# S7CAS-PLEIADES-CARTE-MERE_P07_USB.net
KiCad netlist of a schematic drawn in Altium Designer
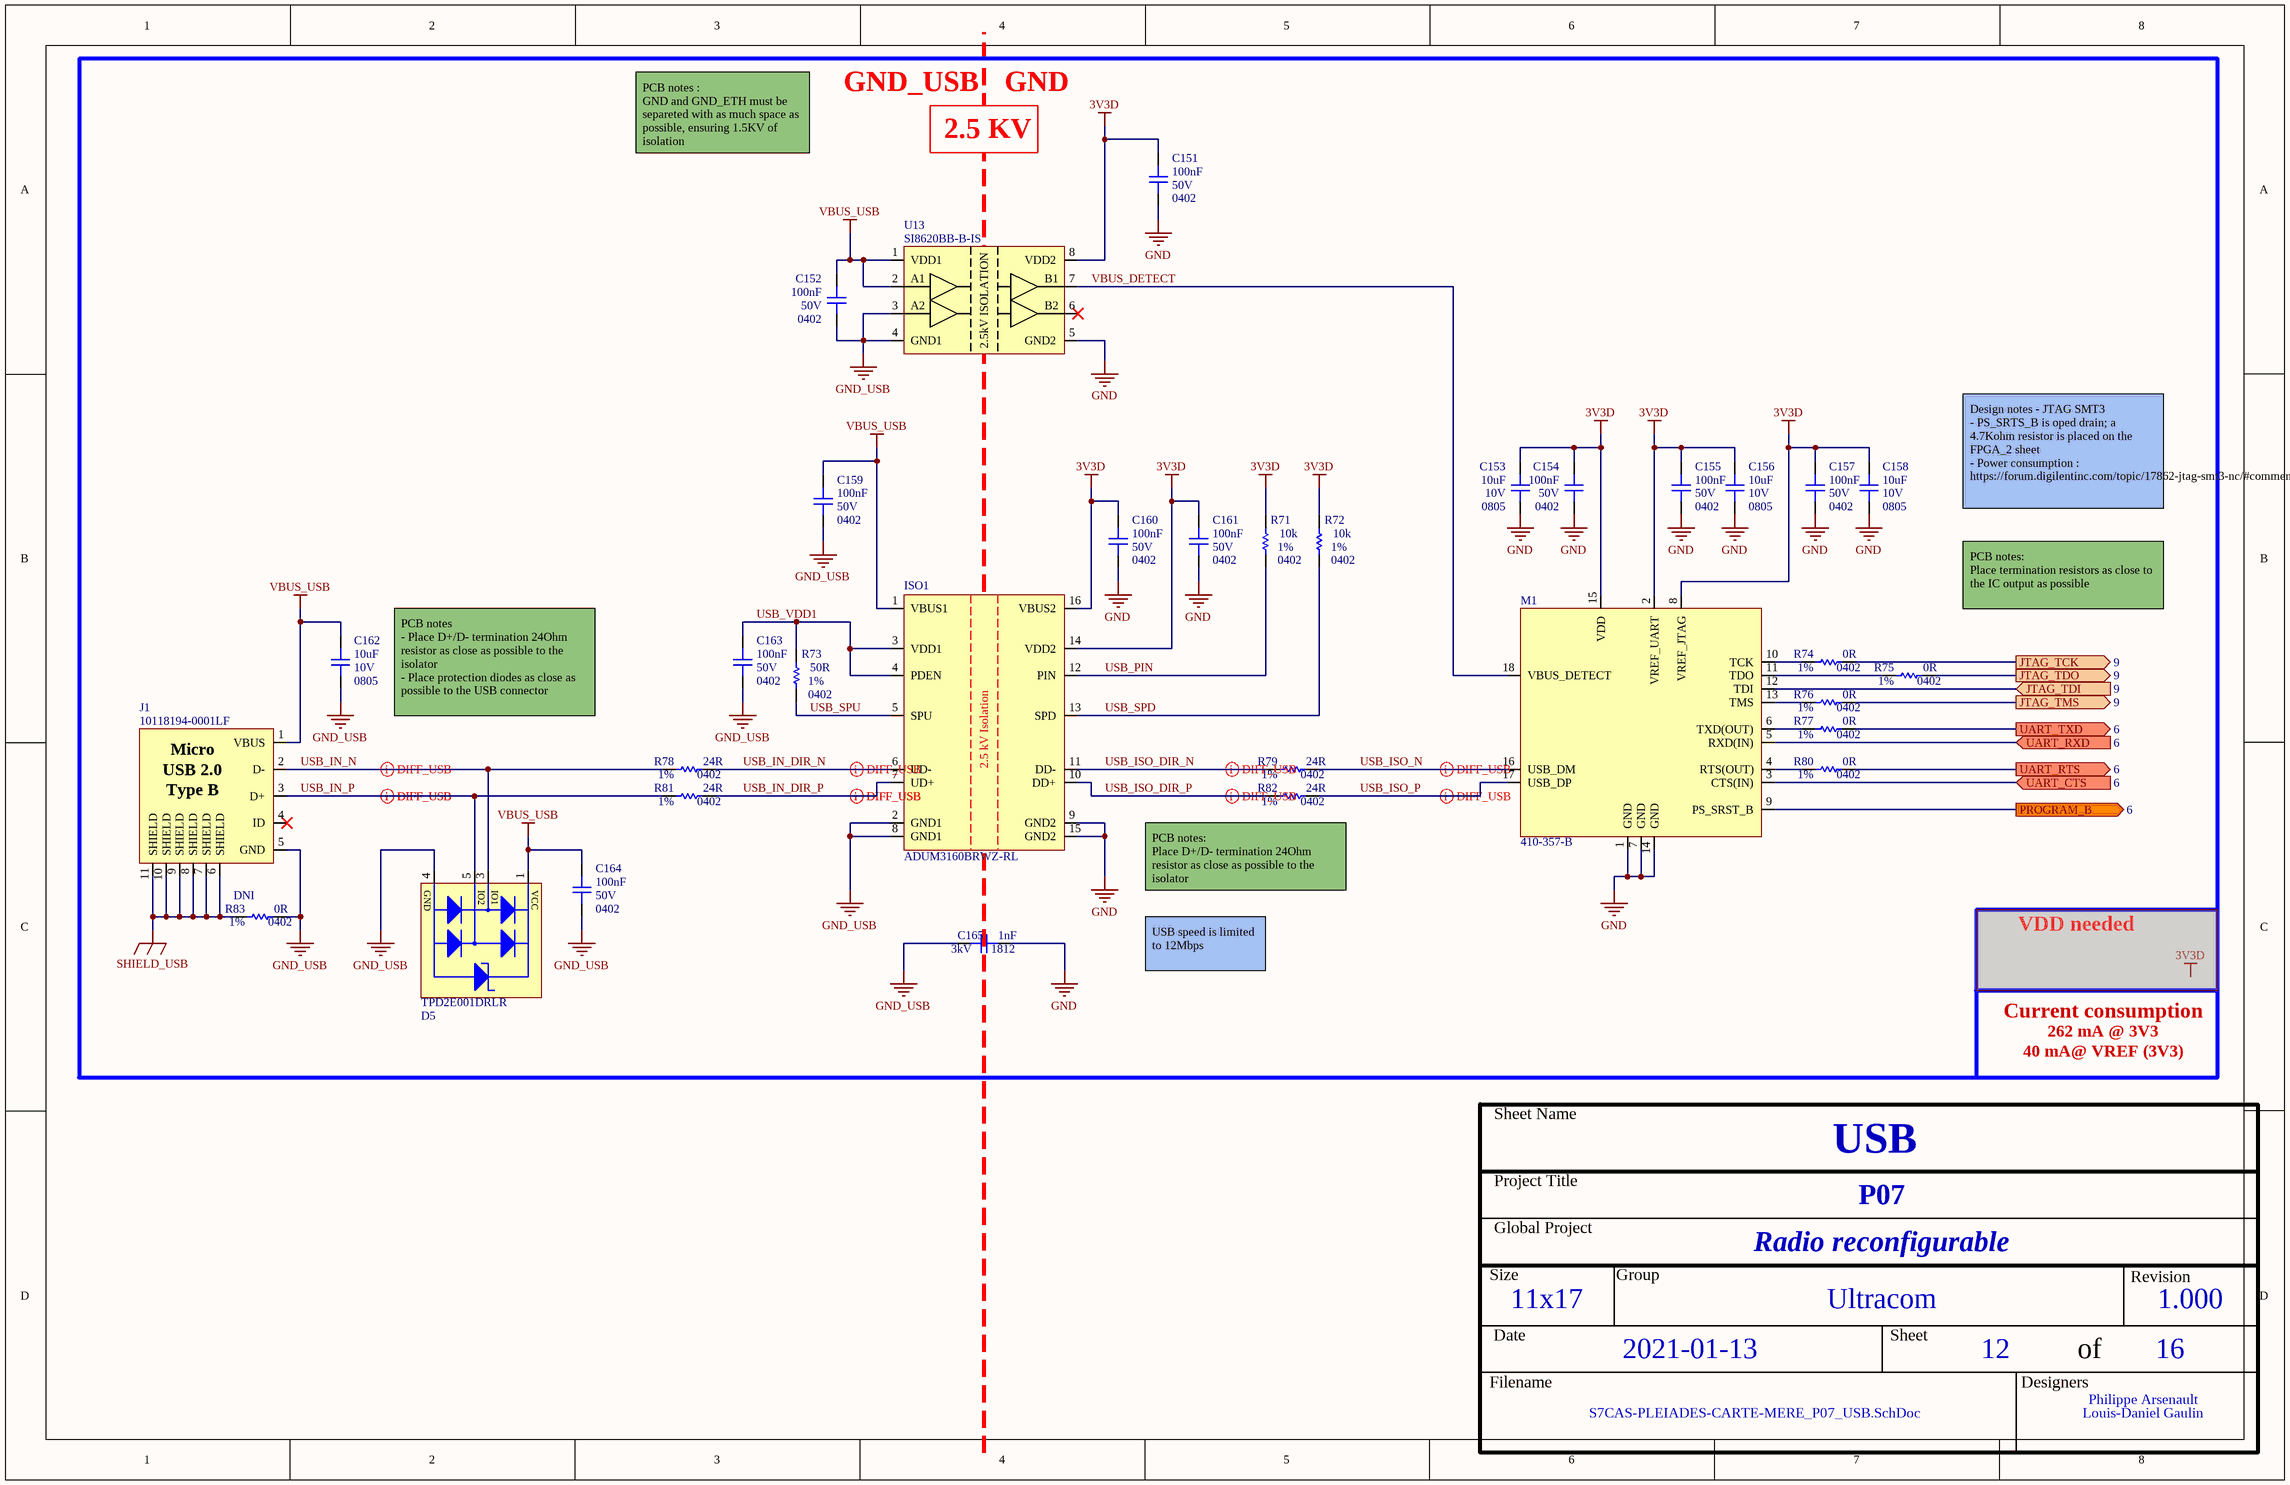
[diagram p0: S7CAS-PLEIADES-CARTE-MERE_P07_USB.SchDoc]

(export (version "E")
  (design (tool "Eeschema 10.0.6"))
  (components
    (comp (ref "C151")
      (value "100nF")
      (footprint "CAP_0402")
      (description "CAP - 0402")
      (fields
        (field (name "VOLTAGE") "50V")
        (field (name "PACKAGE") "0402")
        (field (name "CREATEDBY") "Jonathan Bouchard")
      )
      (libsource (lib "S7CAS_LIB2021") (part "CAP - 0402"))
    )
    (comp (ref "C152")
      (value "100nF")
      (footprint "CAP_0402")
      (description "CAP - 0402")
      (fields
        (field (name "VOLTAGE") "50V")
        (field (name "PACKAGE") "0402")
        (field (name "CREATEDBY") "Jonathan Bouchard")
      )
      (libsource (lib "S7CAS_LIB2021") (part "CAP - 0402"))
    )
    (comp (ref "C153")
      (value "10uF")
      (footprint "CAP_0805")
      (description "CAP - 0805")
      (fields
        (field (name "MFG") "CL21B106KPQNNNE")
        (field (name "VOLTAGE") "10V")
        (field (name "PACKAGE") "0805")
        (field (name "CREATEDBY") "Jonathan Bouchard")
      )
      (libsource (lib "S7CAS_LIB2021") (part "CAP - 0805"))
    )
    (comp (ref "C154")
      (value "100nF")
      (footprint "CAP_0402")
      (description "CAP - 0402")
      (fields
        (field (name "VOLTAGE") "50V")
        (field (name "PACKAGE") "0402")
        (field (name "CREATEDBY") "Jonathan Bouchard")
      )
      (libsource (lib "S7CAS_LIB2021") (part "CAP - 0402"))
    )
    (comp (ref "C155")
      (value "100nF")
      (footprint "CAP_0402")
      (description "CAP - 0402")
      (fields
        (field (name "VOLTAGE") "50V")
        (field (name "PACKAGE") "0402")
        (field (name "CREATEDBY") "Jonathan Bouchard")
      )
      (libsource (lib "S7CAS_LIB2021") (part "CAP - 0402"))
    )
    (comp (ref "C156")
      (value "10uF")
      (footprint "CAP_0805")
      (description "CAP - 0805")
      (fields
        (field (name "MFG") "CL21B106KPQNNNE")
        (field (name "VOLTAGE") "10V")
        (field (name "PACKAGE") "0805")
        (field (name "CREATEDBY") "Jonathan Bouchard")
      )
      (libsource (lib "S7CAS_LIB2021") (part "CAP - 0805"))
    )
    (comp (ref "C157")
      (value "100nF")
      (footprint "CAP_0402")
      (description "CAP - 0402")
      (fields
        (field (name "VOLTAGE") "50V")
        (field (name "PACKAGE") "0402")
        (field (name "CREATEDBY") "Jonathan Bouchard")
      )
      (libsource (lib "S7CAS_LIB2021") (part "CAP - 0402"))
    )
    (comp (ref "C158")
      (value "10uF")
      (footprint "CAP_0805")
      (description "CAP - 0805")
      (fields
        (field (name "MFG") "CL21B106KPQNNNE")
        (field (name "VOLTAGE") "10V")
        (field (name "PACKAGE") "0805")
        (field (name "CREATEDBY") "Jonathan Bouchard")
      )
      (libsource (lib "S7CAS_LIB2021") (part "CAP - 0805"))
    )
    (comp (ref "C159")
      (value "100nF")
      (footprint "CAP_0402")
      (description "CAP - 0402")
      (fields
        (field (name "VOLTAGE") "50V")
        (field (name "PACKAGE") "0402")
        (field (name "CREATEDBY") "Jonathan Bouchard")
      )
      (libsource (lib "S7CAS_LIB2021") (part "CAP - 0402"))
    )
    (comp (ref "C160")
      (value "100nF")
      (footprint "CAP_0402")
      (description "CAP - 0402")
      (fields
        (field (name "VOLTAGE") "50V")
        (field (name "PACKAGE") "0402")
        (field (name "CREATEDBY") "Jonathan Bouchard")
      )
      (libsource (lib "S7CAS_LIB2021") (part "CAP - 0402"))
    )
    (comp (ref "C161")
      (value "100nF")
      (footprint "CAP_0402")
      (description "CAP - 0402")
      (fields
        (field (name "VOLTAGE") "50V")
        (field (name "PACKAGE") "0402")
        (field (name "CREATEDBY") "Jonathan Bouchard")
      )
      (libsource (lib "S7CAS_LIB2021") (part "CAP - 0402"))
    )
    (comp (ref "C162")
      (value "10uF")
      (footprint "CAP_0805")
      (description "CAP - 0805")
      (fields
        (field (name "MFG") "CL21B106KPQNNNE")
        (field (name "VOLTAGE") "10V")
        (field (name "PACKAGE") "0805")
        (field (name "CREATEDBY") "Jonathan Bouchard")
      )
      (libsource (lib "S7CAS_LIB2021") (part "CAP - 0805"))
    )
    (comp (ref "C163")
      (value "100nF")
      (footprint "CAP_0402")
      (description "CAP - 0402")
      (fields
        (field (name "VOLTAGE") "50V")
        (field (name "PACKAGE") "0402")
        (field (name "CREATEDBY") "Jonathan Bouchard")
      )
      (libsource (lib "S7CAS_LIB2021") (part "CAP - 0402"))
    )
    (comp (ref "C164")
      (value "100nF")
      (footprint "CAP_0402")
      (description "CAP - 0402")
      (fields
        (field (name "VOLTAGE") "50V")
        (field (name "PACKAGE") "0402")
        (field (name "CREATEDBY") "Jonathan Bouchard")
      )
      (libsource (lib "S7CAS_LIB2021") (part "CAP - 0402"))
    )
    (comp (ref "C165")
      (value "1nF")
      (footprint "CAP_1812")
      (description "CAP - 1812")
      (fields
        (field (name "MFG PART NUMBER") "1812HC102MAT1A")
        (field (name "VOLTAGE") "3kV")
        (field (name "PACKAGE") "1812")
        (field (name "CREATEDBY") "Jonathan Bouchard")
      )
      (libsource (lib "S7CAS_P07") (part "CAP - 1812"))
    )
    (comp (ref "D5")
      (value "TPD2E001DRLR")
      (footprint "TVS_USB_TPD2E001DRLR")
      (description "TVS - USB TVS DIODE 5.5V - SOT-553")
      (fields
        (field (name "CREATEDBY/DATE") "Jonathan Bouchard 2018-07-10")
        (field (name "VERIFIEDBY") "Arnaud Samson 16-07-18")
      )
      (libsource (lib "S7CAS_LIB2021") (part "TVS_USB_TPD2E001DRLR"))
    )
    (comp (ref "ISO1")
      (value "ADUM3160BRWZ-RL")
      (footprint "ISO_ADUM3160BRWZ-RL")
      (description "ISO - DGTL ISO 2.5KV 2CH USB - 16SOIC")
      (fields
        (field (name "CREATEDBY/DATE") "Tommy Rossignol 2018-11-16")
        (field (name "VERIFIEDBY") "Caroline Paulin - 13 février 2019")
      )
      (libsource (lib "S7CAS_LIB2021") (part "ISO_ADUM3160BRWZ-RL"))
    )
    (comp (ref "J1")
      (value "10118194-0001LF")
      (footprint "CON_USB_10118194-0001LF")
      (description "CON - USB MICRO B RECPT SMT R/A - 4PIN")
      (fields
        (field (name "CREATEDBY/DATE") "Arnaud Samson - 09/07/18")
        (field (name "VERIFIEDBY") "Jonathan Bouchard 2018-07-12")
      )
      (libsource (lib "S7CAS_LIB2021") (part "CON_USB_10118194-0001LF"))
    )
    (comp (ref "M1")
      (value "410-357-B")
      (footprint "MOD_JTAG_410-357-B")
      (description "MOD - JTAG-SMT3-NC Programming Module For Xilinx FPGA - 18-SMT")
      (fields
        (field (name "CREATEDBY/DATE") "Tommy Rossignol 2018-11-23")
        (field (name "VERIFIEDBY") "Nicolas V. (2019-01-28)")
      )
      (libsource (lib "S7CAS_LIB2021") (part "MOD_JTAG_410-357-B"))
    )
    (comp (ref "R71")
      (value "10k")
      (footprint "RES_0402")
      (description "RES - 0402")
      (fields
        (field (name "VOLTAGE") "50V")
        (field (name "POWER") "1/16W")
        (field (name "PACKAGE") "0402")
        (field (name "PRECISION") "1%")
        (field (name "CREATEDBY") "Jonathan Bouchard")
      )
      (libsource (lib "S7CAS_LIB2021") (part "RES - 0402"))
    )
    (comp (ref "R72")
      (value "10k")
      (footprint "RES_0402")
      (description "RES - 0402")
      (fields
        (field (name "VOLTAGE") "50V")
        (field (name "POWER") "1/16W")
        (field (name "PACKAGE") "0402")
        (field (name "PRECISION") "1%")
        (field (name "CREATEDBY") "Jonathan Bouchard")
      )
      (libsource (lib "S7CAS_LIB2021") (part "RES - 0402"))
    )
    (comp (ref "R73")
      (value "50R")
      (footprint "RES_0402")
      (description "RES - 0402")
      (fields
        (field (name "VOLTAGE") "50V")
        (field (name "POWER") "1/16W")
        (field (name "PACKAGE") "0402")
        (field (name "PRECISION") "1%")
        (field (name "CREATEDBY") "Jonathan Bouchard")
      )
      (libsource (lib "S7CAS_LIB2021") (part "RES - 0402"))
    )
    (comp (ref "R74")
      (value "0R")
      (footprint "RES_0402")
      (description "RES - 0402")
      (fields
        (field (name "VOLTAGE") "50V")
        (field (name "POWER") "1/16W")
        (field (name "PACKAGE") "0402")
        (field (name "PRECISION") "1%")
        (field (name "CREATEDBY") "Jonathan Bouchard")
      )
      (libsource (lib "S7CAS_LIB2021") (part "RES - 0402"))
    )
    (comp (ref "R75")
      (value "0R")
      (footprint "RES_0402")
      (description "RES - 0402")
      (fields
        (field (name "VOLTAGE") "50V")
        (field (name "POWER") "1/16W")
        (field (name "PACKAGE") "0402")
        (field (name "PRECISION") "1%")
        (field (name "CREATEDBY") "Jonathan Bouchard")
      )
      (libsource (lib "S7CAS_LIB2021") (part "RES - 0402"))
    )
    (comp (ref "R76")
      (value "0R")
      (footprint "RES_0402")
      (description "RES - 0402")
      (fields
        (field (name "VOLTAGE") "50V")
        (field (name "POWER") "1/16W")
        (field (name "PACKAGE") "0402")
        (field (name "PRECISION") "1%")
        (field (name "CREATEDBY") "Jonathan Bouchard")
      )
      (libsource (lib "S7CAS_LIB2021") (part "RES - 0402"))
    )
    (comp (ref "R77")
      (value "0R")
      (footprint "RES_0402")
      (description "RES - 0402")
      (fields
        (field (name "VOLTAGE") "50V")
        (field (name "POWER") "1/16W")
        (field (name "PACKAGE") "0402")
        (field (name "PRECISION") "1%")
        (field (name "CREATEDBY") "Jonathan Bouchard")
      )
      (libsource (lib "S7CAS_LIB2021") (part "RES - 0402"))
    )
    (comp (ref "R78")
      (value "24R")
      (footprint "RES_0402")
      (description "RES - 0402")
      (fields
        (field (name "VOLTAGE") "50V")
        (field (name "POWER") "1/16W")
        (field (name "PACKAGE") "0402")
        (field (name "PRECISION") "1%")
        (field (name "CREATEDBY") "Jonathan Bouchard")
      )
      (libsource (lib "S7CAS_LIB2021") (part "RES - 0402"))
    )
    (comp (ref "R79")
      (value "24R")
      (footprint "RES_0402")
      (description "RES - 0402")
      (fields
        (field (name "VOLTAGE") "50V")
        (field (name "POWER") "1/16W")
        (field (name "PACKAGE") "0402")
        (field (name "PRECISION") "1%")
        (field (name "CREATEDBY") "Jonathan Bouchard")
      )
      (libsource (lib "S7CAS_LIB2021") (part "RES - 0402"))
    )
    (comp (ref "R80")
      (value "0R")
      (footprint "RES_0402")
      (description "RES - 0402")
      (fields
        (field (name "VOLTAGE") "50V")
        (field (name "POWER") "1/16W")
        (field (name "PACKAGE") "0402")
        (field (name "PRECISION") "1%")
        (field (name "CREATEDBY") "Jonathan Bouchard")
      )
      (libsource (lib "S7CAS_LIB2021") (part "RES - 0402"))
    )
    (comp (ref "R81")
      (value "24R")
      (footprint "RES_0402")
      (description "RES - 0402")
      (fields
        (field (name "VOLTAGE") "50V")
        (field (name "POWER") "1/16W")
        (field (name "PACKAGE") "0402")
        (field (name "PRECISION") "1%")
        (field (name "CREATEDBY") "Jonathan Bouchard")
      )
      (libsource (lib "S7CAS_LIB2021") (part "RES - 0402"))
    )
    (comp (ref "R82")
      (value "24R")
      (footprint "RES_0402")
      (description "RES - 0402")
      (fields
        (field (name "VOLTAGE") "50V")
        (field (name "POWER") "1/16W")
        (field (name "PACKAGE") "0402")
        (field (name "PRECISION") "1%")
        (field (name "CREATEDBY") "Jonathan Bouchard")
      )
      (libsource (lib "S7CAS_LIB2021") (part "RES - 0402"))
    )
    (comp (ref "R83")
      (value "0R")
      (footprint "RES_0402")
      (description "RES - 0402")
      (fields
        (field (name "VOLTAGE") "50V")
        (field (name "POWER") "1/16W")
        (field (name "PACKAGE") "0402")
        (field (name "PRECISION") "1%")
        (field (name "ASSEMBLY NOTE") "DNI")
        (field (name "CREATEDBY") "Jonathan Bouchard")
      )
      (libsource (lib "S7CAS_LIB2021") (part "RES - 0402"))
    )
    (comp (ref "U13")
      (value "SI8620BB-B-IS")
      (footprint "ISO_SI8620BB-B-IS")
      (description "ISO - Dual-Channel Digital Isolator (default Low) - 8-SOIC")
      (fields
        (field (name "CREATEDBY/DATE") "Joel Lemay 2018-06-05")
        (field (name "VERIFIEDBY") "Caroline Paulin - 12 sept 2018")
      )
      (libsource (lib "S7CAS_LIB2021") (part "ISO_SI8620BB-B-IS"))
    )
  )
  (nets
    (net (code "1") (name "/JTAG_TCK") (class "Default")
      (node (ref "R74") (pin "1") (pinfunction "1_1") (pintype "passive"))
    )
    (net (code "2") (name "/JTAG_TDI") (class "Default")
      (node (ref "M1") (pin "12") (pinfunction "TDI_12") (pintype "passive"))
    )
    (net (code "3") (name "/JTAG_TDO") (class "Default")
      (node (ref "R75") (pin "1") (pinfunction "1_1") (pintype "passive"))
    )
    (net (code "4") (name "/JTAG_TMS") (class "Default")
      (node (ref "R76") (pin "1") (pinfunction "1_1") (pintype "passive"))
    )
    (net (code "5") (name "/PROGRAM_B") (class "Default")
      (node (ref "M1") (pin "9") (pinfunction "PS_SRST_B_9") (pintype "passive"))
    )
    (net (code "6") (name "/UART_CTS") (class "Default")
      (node (ref "M1") (pin "3") (pinfunction "CTS(IN)_3") (pintype "passive"))
    )
    (net (code "7") (name "/UART_RTS") (class "Default")
      (node (ref "R80") (pin "1") (pinfunction "1_1") (pintype "passive"))
    )
    (net (code "8") (name "/UART_RXD") (class "Default")
      (node (ref "M1") (pin "5") (pinfunction "RXD(IN)_5") (pintype "passive"))
    )
    (net (code "9") (name "/UART_TXD") (class "Default")
      (node (ref "R77") (pin "1") (pinfunction "1_1") (pintype "passive"))
    )
    (net (code "10") (name "/USB_IN_DIR_N") (class "Default")
      (node (ref "ISO1") (pin "6") (pinfunction "UD-_6") (pintype "passive"))
      (node (ref "R78") (pin "1") (pinfunction "1_1") (pintype "passive"))
    )
    (net (code "11") (name "/USB_IN_DIR_P") (class "Default")
      (node (ref "ISO1") (pin "7") (pinfunction "UD+_7") (pintype "passive"))
      (node (ref "R81") (pin "1") (pinfunction "1_1") (pintype "passive"))
    )
    (net (code "12") (name "/USB_IN_N") (class "Default")
      (node (ref "D5") (pin "3") (pinfunction "IO1_3") (pintype "passive"))
      (node (ref "J1") (pin "2") (pinfunction "D-_2") (pintype "passive"))
      (node (ref "R78") (pin "2") (pinfunction "2_2") (pintype "passive"))
    )
    (net (code "13") (name "/USB_IN_P") (class "Default")
      (node (ref "D5") (pin "5") (pinfunction "IO2_5") (pintype "passive"))
      (node (ref "J1") (pin "3") (pinfunction "D+_3") (pintype "passive"))
      (node (ref "R81") (pin "2") (pinfunction "2_2") (pintype "passive"))
    )
    (net (code "14") (name "/USB_ISO_DIR_N") (class "Default")
      (node (ref "ISO1") (pin "11") (pinfunction "DD-_11") (pintype "passive"))
      (node (ref "R79") (pin "2") (pinfunction "2_2") (pintype "passive"))
    )
    (net (code "15") (name "/USB_ISO_DIR_P") (class "Default")
      (node (ref "ISO1") (pin "10") (pinfunction "DD+_10") (pintype "passive"))
      (node (ref "R82") (pin "2") (pinfunction "2_2") (pintype "passive"))
    )
    (net (code "16") (name "/USB_ISO_N") (class "Default")
      (node (ref "M1") (pin "16") (pinfunction "USB_DM_16") (pintype "passive"))
      (node (ref "R79") (pin "1") (pinfunction "1_1") (pintype "passive"))
    )
    (net (code "17") (name "/USB_ISO_P") (class "Default")
      (node (ref "M1") (pin "17") (pinfunction "USB_DP_17") (pintype "passive"))
      (node (ref "R82") (pin "1") (pinfunction "1_1") (pintype "passive"))
    )
    (net (code "18") (name "/USB_PIN") (class "Default")
      (node (ref "ISO1") (pin "12") (pinfunction "PIN_12") (pintype "passive"))
      (node (ref "R71") (pin "1") (pinfunction "1_1") (pintype "passive"))
    )
    (net (code "19") (name "/USB_SPD") (class "Default")
      (node (ref "ISO1") (pin "13") (pinfunction "SPD_13") (pintype "passive"))
      (node (ref "R72") (pin "1") (pinfunction "1_1") (pintype "passive"))
    )
    (net (code "20") (name "/USB_SPU") (class "Default")
      (node (ref "ISO1") (pin "5") (pinfunction "SPU_5") (pintype "passive"))
      (node (ref "R73") (pin "1") (pinfunction "1_1") (pintype "passive"))
    )
    (net (code "21") (name "/USB_VDD1") (class "Default")
      (node (ref "C163") (pin "2") (pinfunction "2_2") (pintype "passive"))
      (node (ref "ISO1") (pin "3") (pinfunction "VDD1_3") (pintype "passive"))
      (node (ref "ISO1") (pin "4") (pinfunction "PDEN_4") (pintype "passive"))
      (node (ref "R73") (pin "2") (pinfunction "2_2") (pintype "passive"))
    )
    (net (code "22") (name "/VBUS_DETECT") (class "Default")
      (node (ref "M1") (pin "18") (pinfunction "VBUS_DETECT_18") (pintype "passive"))
      (node (ref "U13") (pin "7") (pinfunction "B1_7") (pintype "passive"))
    )
    (net (code "23") (name "3V3D") (class "Default")
      (node (ref "C151") (pin "2") (pinfunction "2_2") (pintype "passive"))
      (node (ref "C153") (pin "2") (pinfunction "2_2") (pintype "passive"))
      (node (ref "C154") (pin "2") (pinfunction "2_2") (pintype "passive"))
      (node (ref "C155") (pin "2") (pinfunction "2_2") (pintype "passive"))
      (node (ref "C156") (pin "2") (pinfunction "2_2") (pintype "passive"))
      (node (ref "C157") (pin "2") (pinfunction "2_2") (pintype "passive"))
      (node (ref "C158") (pin "2") (pinfunction "2_2") (pintype "passive"))
      (node (ref "C160") (pin "2") (pinfunction "2_2") (pintype "passive"))
      (node (ref "C161") (pin "2") (pinfunction "2_2") (pintype "passive"))
      (node (ref "ISO1") (pin "14") (pinfunction "VDD2_14") (pintype "passive"))
      (node (ref "ISO1") (pin "16") (pinfunction "VBUS2_16") (pintype "passive"))
      (node (ref "M1") (pin "15") (pinfunction "VDD_15") (pintype "passive"))
      (node (ref "M1") (pin "2") (pinfunction "VREF_UART_2") (pintype "passive"))
      (node (ref "M1") (pin "8") (pinfunction "VREF_JTAG_8") (pintype "passive"))
      (node (ref "R71") (pin "2") (pinfunction "2_2") (pintype "passive"))
      (node (ref "R72") (pin "2") (pinfunction "2_2") (pintype "passive"))
      (node (ref "U13") (pin "8") (pinfunction "VDD2_8") (pintype "passive"))
    )
    (net (code "24") (name "GND") (class "Default")
      (node (ref "C151") (pin "1") (pinfunction "1_1") (pintype "passive"))
      (node (ref "C153") (pin "1") (pinfunction "1_1") (pintype "passive"))
      (node (ref "C154") (pin "1") (pinfunction "1_1") (pintype "passive"))
      (node (ref "C155") (pin "1") (pinfunction "1_1") (pintype "passive"))
      (node (ref "C156") (pin "1") (pinfunction "1_1") (pintype "passive"))
      (node (ref "C157") (pin "1") (pinfunction "1_1") (pintype "passive"))
      (node (ref "C158") (pin "1") (pinfunction "1_1") (pintype "passive"))
      (node (ref "C160") (pin "1") (pinfunction "1_1") (pintype "passive"))
      (node (ref "C161") (pin "1") (pinfunction "1_1") (pintype "passive"))
      (node (ref "C165") (pin "1") (pinfunction "1_1") (pintype "passive"))
      (node (ref "ISO1") (pin "15") (pinfunction "GND2_15") (pintype "passive"))
      (node (ref "ISO1") (pin "9") (pinfunction "GND2_9") (pintype "passive"))
      (node (ref "M1") (pin "1") (pinfunction "GND_1") (pintype "passive"))
      (node (ref "M1") (pin "14") (pinfunction "GND_14") (pintype "passive"))
      (node (ref "M1") (pin "7") (pinfunction "GND_7") (pintype "passive"))
      (node (ref "U13") (pin "5") (pinfunction "GND2_5") (pintype "passive"))
    )
    (net (code "25") (name "GND_USB") (class "Default")
      (node (ref "C152") (pin "1") (pinfunction "1_1") (pintype "passive"))
      (node (ref "C159") (pin "1") (pinfunction "1_1") (pintype "passive"))
      (node (ref "C162") (pin "1") (pinfunction "1_1") (pintype "passive"))
      (node (ref "C163") (pin "1") (pinfunction "1_1") (pintype "passive"))
      (node (ref "C164") (pin "1") (pinfunction "1_1") (pintype "passive"))
      (node (ref "C165") (pin "2") (pinfunction "2_2") (pintype "passive"))
      (node (ref "D5") (pin "4") (pinfunction "GND_4") (pintype "passive"))
      (node (ref "ISO1") (pin "2") (pinfunction "GND1_2") (pintype "passive"))
      (node (ref "ISO1") (pin "8") (pinfunction "GND1_8") (pintype "passive"))
      (node (ref "J1") (pin "5") (pinfunction "GND_5") (pintype "passive"))
      (node (ref "R83") (pin "1") (pinfunction "1_1") (pintype "passive"))
      (node (ref "U13") (pin "3") (pinfunction "A2_3") (pintype "passive"))
      (node (ref "U13") (pin "4") (pinfunction "GND1_4") (pintype "passive"))
    )
    (net (code "26") (name "Net-(M1-RTS(OUT))") (class "Default")
      (node (ref "M1") (pin "4") (pinfunction "RTS(OUT)_4") (pintype "passive"))
      (node (ref "R80") (pin "2") (pinfunction "2_2") (pintype "passive"))
    )
    (net (code "27") (name "Net-(M1-TCK)") (class "Default")
      (node (ref "M1") (pin "10") (pinfunction "TCK_10") (pintype "passive"))
      (node (ref "R74") (pin "2") (pinfunction "2_2") (pintype "passive"))
    )
    (net (code "28") (name "Net-(M1-TDO)") (class "Default")
      (node (ref "M1") (pin "11") (pinfunction "TDO_11") (pintype "passive"))
      (node (ref "R75") (pin "2") (pinfunction "2_2") (pintype "passive"))
    )
    (net (code "29") (name "Net-(M1-TMS)") (class "Default")
      (node (ref "M1") (pin "13") (pinfunction "TMS_13") (pintype "passive"))
      (node (ref "R76") (pin "2") (pinfunction "2_2") (pintype "passive"))
    )
    (net (code "30") (name "Net-(M1-TXD(OUT))") (class "Default")
      (node (ref "M1") (pin "6") (pinfunction "TXD(OUT)_6") (pintype "passive"))
      (node (ref "R77") (pin "2") (pinfunction "2_2") (pintype "passive"))
    )
    (net (code "31") (name "SHIELD_USB") (class "Default")
      (node (ref "J1") (pin "10") (pinfunction "SHIELD_10") (pintype "passive"))
      (node (ref "J1") (pin "11") (pinfunction "SHIELD_11") (pintype "passive"))
      (node (ref "J1") (pin "6") (pinfunction "SHIELD_6") (pintype "passive"))
      (node (ref "J1") (pin "7") (pinfunction "SHIELD_7") (pintype "passive"))
      (node (ref "J1") (pin "8") (pinfunction "SHIELD_8") (pintype "passive"))
      (node (ref "J1") (pin "9") (pinfunction "SHIELD_9") (pintype "passive"))
      (node (ref "R83") (pin "2") (pinfunction "2_2") (pintype "passive"))
    )
    (net (code "32") (name "VBUS_USB") (class "Default")
      (node (ref "C152") (pin "2") (pinfunction "2_2") (pintype "passive"))
      (node (ref "C159") (pin "2") (pinfunction "2_2") (pintype "passive"))
      (node (ref "C162") (pin "2") (pinfunction "2_2") (pintype "passive"))
      (node (ref "C164") (pin "2") (pinfunction "2_2") (pintype "passive"))
      (node (ref "D5") (pin "1") (pinfunction "VCC_1") (pintype "passive"))
      (node (ref "ISO1") (pin "1") (pinfunction "VBUS1_1") (pintype "passive"))
      (node (ref "J1") (pin "1") (pinfunction "VBUS_1") (pintype "passive"))
      (node (ref "U13") (pin "1") (pinfunction "VDD1_1") (pintype "passive"))
      (node (ref "U13") (pin "2") (pinfunction "A1_2") (pintype "passive"))
    )
    (net (code "33") (name "unconnected-(D5-NC-Pad2)") (class "Default")
      (node (ref "D5") (pin "2") (pinfunction "NC_2") (pintype "passive"))
    )
    (net (code "34") (name "unconnected-(J1-ID-Pad4)") (class "Default")
      (node (ref "J1") (pin "4") (pinfunction "ID_4") (pintype "passive+no_connect"))
    )
    (net (code "35") (name "unconnected-(U13-B2-Pad6)") (class "Default")
      (node (ref "U13") (pin "6") (pinfunction "B2_6") (pintype "passive+no_connect"))
    )
  )
)
